# Stepper_L647x.net
KiCad netlist of a schematic drawn in EAGLE
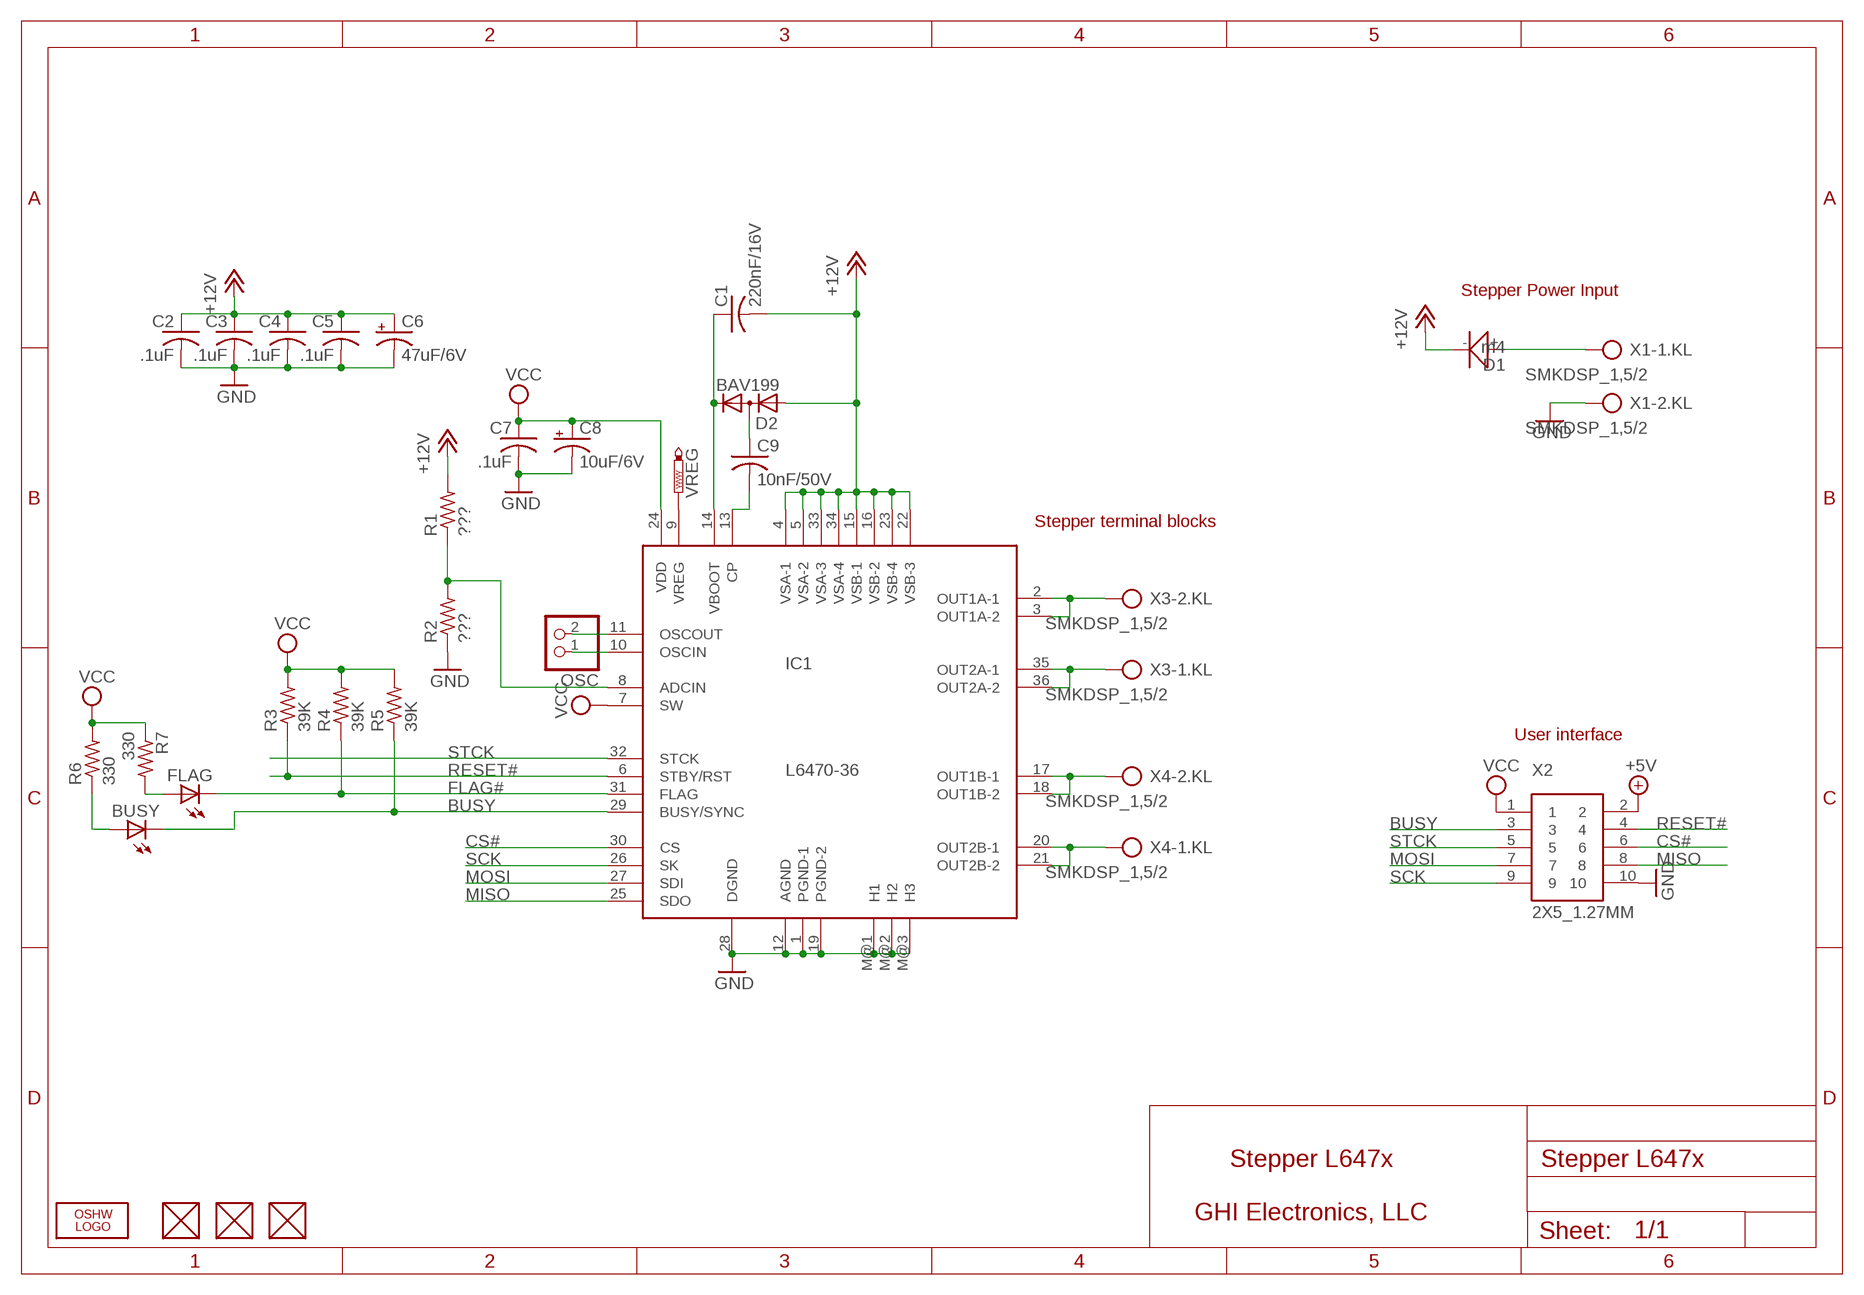
[diagram p0: schematic, sheet 1]

(export (version "E")
  (design (tool "Eeschema 10.0.6"))
  (components
    (comp (ref "BUSY")
      (value "LEDCHIPLED_0805")
      (footprint "eagle-import:CHIPLED_0805")
      (libsource (lib "eagle-import") (part "LEDCHIPLED_0805"))
    )
    (comp (ref "C1")
      (value "220nF/16V")
      (footprint "eagle-import:C0603K")
      (libsource (lib "eagle-import") (part "C-USC0603K"))
    )
    (comp (ref "C2")
      (value ".1uF")
      (footprint "eagle-import:C0603K")
      (libsource (lib "eagle-import") (part "C-USC0603K"))
    )
    (comp (ref "C3")
      (value ".1uF")
      (footprint "eagle-import:C0603K")
      (libsource (lib "eagle-import") (part "C-USC0603K"))
    )
    (comp (ref "C4")
      (value ".1uF")
      (footprint "eagle-import:C0603K")
      (libsource (lib "eagle-import") (part "C-USC0603K"))
    )
    (comp (ref "C5")
      (value ".1uF")
      (footprint "eagle-import:C0603K")
      (libsource (lib "eagle-import") (part "C-USC0603K"))
    )
    (comp (ref "C6")
      (value "47uF/6V")
      (footprint "eagle-import:CT3528")
      (libsource (lib "eagle-import") (part "CPOL-USCT3528"))
    )
    (comp (ref "C7")
      (value ".1uF")
      (footprint "eagle-import:C0603K")
      (libsource (lib "eagle-import") (part "C-USC0603K"))
    )
    (comp (ref "C8")
      (value "10uF/6V")
      (footprint "eagle-import:CT3528")
      (libsource (lib "eagle-import") (part "CPOL-USCT3528"))
    )
    (comp (ref "C9")
      (value "10nF/50V")
      (footprint "eagle-import:C0603K")
      (libsource (lib "eagle-import") (part "C-USC0603K"))
    )
    (comp (ref "D1")
      (value "m4")
      (footprint "eagle-import:D2010")
      (libsource (lib "eagle-import") (part "010-D2010"))
    )
    (comp (ref "D2")
      (value "BAV199")
      (footprint "eagle-import:SOT23")
      (libsource (lib "eagle-import") (part "BAV199"))
    )
    (comp (ref "FLAG")
      (value "LEDCHIPLED_0805")
      (footprint "eagle-import:CHIPLED_0805")
      (libsource (lib "eagle-import") (part "LEDCHIPLED_0805"))
    )
    (comp (ref "FUD1")
      (value "FIDUCIAL")
      (footprint "eagle-import:FIDUCIAL_40MIL")
      (libsource (lib "eagle-import") (part "FIDUCIAL"))
    )
    (comp (ref "FUD2")
      (value "FIDUCIAL")
      (footprint "eagle-import:FIDUCIAL_40MIL")
      (libsource (lib "eagle-import") (part "FIDUCIAL"))
    )
    (comp (ref "FUD3")
      (value "FIDUCIAL")
      (footprint "eagle-import:FIDUCIAL_40MIL")
      (libsource (lib "eagle-import") (part "FIDUCIAL"))
    )
    (comp (ref "IC1")
      (value "L6470-36")
      (footprint "eagle-import:PSO36")
      (libsource (lib "eagle-import") (part "L6470-36"))
    )
    (comp (ref "LOGO1")
      (value "LOGO-OSHW-FILLX0200-NT")
      (footprint "eagle-import:OSHW_FILLX200_NOTEXT")
      (libsource (lib "eagle-import") (part "LOGO-OSHW-FILLX0200-NT"))
    )
    (comp (ref "OSC")
      (value "PINHD-1X2")
      (footprint "eagle-import:1X02")
      (libsource (lib "eagle-import") (part "PINHD-1X2"))
    )
    (comp (ref "R1")
      (value "???")
      (footprint "eagle-import:R0603")
      (libsource (lib "eagle-import") (part "R-US_R0603"))
    )
    (comp (ref "R2")
      (value "???")
      (footprint "eagle-import:R0603")
      (libsource (lib "eagle-import") (part "R-US_R0603"))
    )
    (comp (ref "R3")
      (value "39K")
      (footprint "eagle-import:R0603")
      (libsource (lib "eagle-import") (part "R-US_R0603"))
    )
    (comp (ref "R4")
      (value "39K")
      (footprint "eagle-import:R0603")
      (libsource (lib "eagle-import") (part "R-US_R0603"))
    )
    (comp (ref "R5")
      (value "39K")
      (footprint "eagle-import:R0603")
      (libsource (lib "eagle-import") (part "R-US_R0603"))
    )
    (comp (ref "R6")
      (value "330")
      (footprint "eagle-import:R0603")
      (libsource (lib "eagle-import") (part "R-US_R0603"))
    )
    (comp (ref "R7")
      (value "330")
      (footprint "eagle-import:R0603")
      (libsource (lib "eagle-import") (part "R-US_R0603"))
    )
    (comp (ref "VREG")
      (value "PTR1PAD1-13")
      (footprint "eagle-import:P1-13")
      (libsource (lib "eagle-import") (part "PTR1PAD1-13"))
    )
    (comp (ref "X1")
      (value "SMKDSP_1,5/2")
      (footprint "eagle-import:SMKDSP_1,5_2")
      (libsource (lib "eagle-import") (part "SMKDSP_1,5/2"))
    )
    (comp (ref "X2")
      (value "2X5_1.27MM")
      (footprint "eagle-import:2X5_1.27MM")
      (libsource (lib "eagle-import") (part "2X5_1.27MM"))
    )
    (comp (ref "X3")
      (value "SMKDSP_1,5/2")
      (footprint "eagle-import:SMKDSP_1,5_2")
      (libsource (lib "eagle-import") (part "SMKDSP_1,5/2"))
    )
    (comp (ref "X4")
      (value "SMKDSP_1,5/2")
      (footprint "eagle-import:SMKDSP_1,5_2")
      (libsource (lib "eagle-import") (part "SMKDSP_1,5/2"))
    )
  )
  (nets
    (net (code "1") (name "+5V") (class "Default")
      (node (ref "X2") (pin "2") (pinfunction "2_2") (pintype "bidirectional"))
    )
    (net (code "2") (name "+12V") (class "Default")
      (node (ref "C1") (pin "2") (pinfunction "2_2") (pintype "passive"))
      (node (ref "C2") (pin "1") (pinfunction "1_1") (pintype "passive"))
      (node (ref "C3") (pin "1") (pinfunction "1_1") (pintype "passive"))
      (node (ref "C4") (pin "1") (pinfunction "1_1") (pintype "passive"))
      (node (ref "C5") (pin "1") (pinfunction "1_1") (pintype "passive"))
      (node (ref "C6") (pin "+") (pinfunction "+_+") (pintype "passive"))
      (node (ref "D1") (pin "-") (pinfunction "-_-") (pintype "passive"))
      (node (ref "D2") (pin "1") (pinfunction "A_1") (pintype "passive"))
      (node (ref "IC1") (pin "15") (pinfunction "VSB-1_15") (pintype "bidirectional"))
      (node (ref "IC1") (pin "16") (pinfunction "VSB-2_16") (pintype "bidirectional"))
      (node (ref "IC1") (pin "22") (pinfunction "VSB-3_22") (pintype "bidirectional"))
      (node (ref "IC1") (pin "23") (pinfunction "VSB-4_23") (pintype "bidirectional"))
      (node (ref "IC1") (pin "33") (pinfunction "VSA-3_33") (pintype "bidirectional"))
      (node (ref "IC1") (pin "34") (pinfunction "VSA-4_34") (pintype "bidirectional"))
      (node (ref "IC1") (pin "4") (pinfunction "VSA-1_4") (pintype "bidirectional"))
      (node (ref "IC1") (pin "5") (pinfunction "VSA-2_5") (pintype "bidirectional"))
      (node (ref "R1") (pin "2") (pinfunction "2_2") (pintype "passive"))
    )
    (net (code "3") (name "/BUSY") (class "Default")
      (node (ref "BUSY") (pin "C") (pinfunction "C_C") (pintype "passive"))
      (node (ref "IC1") (pin "29") (pinfunction "BUSY/SYNC_29") (pintype "bidirectional"))
      (node (ref "R5") (pin "1") (pinfunction "1_1") (pintype "passive"))
      (node (ref "X2") (pin "3") (pinfunction "3_3") (pintype "bidirectional"))
    )
    (net (code "4") (name "/CS#") (class "Default")
      (node (ref "IC1") (pin "30") (pinfunction "CS_30") (pintype "bidirectional"))
      (node (ref "X2") (pin "6") (pinfunction "6_6") (pintype "bidirectional"))
    )
    (net (code "5") (name "/FLAG#") (class "Default")
      (node (ref "FLAG") (pin "C") (pinfunction "C_C") (pintype "passive"))
      (node (ref "IC1") (pin "31") (pinfunction "FLAG_31") (pintype "bidirectional"))
      (node (ref "R4") (pin "1") (pinfunction "1_1") (pintype "passive"))
    )
    (net (code "6") (name "/MISO") (class "Default")
      (node (ref "IC1") (pin "25") (pinfunction "SDO_25") (pintype "bidirectional"))
      (node (ref "X2") (pin "8") (pinfunction "8_8") (pintype "bidirectional"))
    )
    (net (code "7") (name "/MOSI") (class "Default")
      (node (ref "IC1") (pin "27") (pinfunction "SDI_27") (pintype "bidirectional"))
      (node (ref "X2") (pin "7") (pinfunction "7_7") (pintype "bidirectional"))
    )
    (net (code "8") (name "/RESET#") (class "Default")
      (node (ref "IC1") (pin "6") (pinfunction "STBY/RST_6") (pintype "bidirectional"))
      (node (ref "R3") (pin "1") (pinfunction "1_1") (pintype "passive"))
      (node (ref "X2") (pin "4") (pinfunction "4_4") (pintype "bidirectional"))
    )
    (net (code "9") (name "/SCK") (class "Default")
      (node (ref "IC1") (pin "26") (pinfunction "SK_26") (pintype "bidirectional"))
      (node (ref "X2") (pin "9") (pinfunction "9_9") (pintype "bidirectional"))
    )
    (net (code "10") (name "/STCK") (class "Default")
      (node (ref "IC1") (pin "32") (pinfunction "STCK_32") (pintype "bidirectional"))
      (node (ref "X2") (pin "5") (pinfunction "5_5") (pintype "bidirectional"))
    )
    (net (code "11") (name "GND") (class "Default")
      (node (ref "C2") (pin "2") (pinfunction "2_2") (pintype "passive"))
      (node (ref "C3") (pin "2") (pinfunction "2_2") (pintype "passive"))
      (node (ref "C4") (pin "2") (pinfunction "2_2") (pintype "passive"))
      (node (ref "C5") (pin "2") (pinfunction "2_2") (pintype "passive"))
      (node (ref "C6") (pin "-") (pinfunction "-_-") (pintype "passive"))
      (node (ref "C7") (pin "2") (pinfunction "2_2") (pintype "passive"))
      (node (ref "C8") (pin "-") (pinfunction "-_-") (pintype "passive"))
      (node (ref "IC1") (pin "1") (pinfunction "PGND-1_1") (pintype "bidirectional"))
      (node (ref "IC1") (pin "12") (pinfunction "AGND_12") (pintype "bidirectional"))
      (node (ref "IC1") (pin "19") (pinfunction "PGND-2_19") (pintype "bidirectional"))
      (node (ref "IC1") (pin "28") (pinfunction "DGND_28") (pintype "bidirectional"))
      (node (ref "IC1") (pin "M@1") (pinfunction "H1_M@1") (pintype "bidirectional"))
      (node (ref "IC1") (pin "M@2") (pinfunction "H2_M@2") (pintype "bidirectional"))
      (node (ref "IC1") (pin "M@3") (pinfunction "H3_M@3") (pintype "bidirectional"))
      (node (ref "R2") (pin "1") (pinfunction "1_1") (pintype "passive"))
      (node (ref "X1") (pin "2") (pinfunction "KL_2") (pintype "passive"))
      (node (ref "X2") (pin "10") (pinfunction "10_10") (pintype "bidirectional"))
    )
    (net (code "12") (name "Net-(BUSY-PadA)") (class "Default")
      (node (ref "BUSY") (pin "A") (pinfunction "A_A") (pintype "passive"))
      (node (ref "R6") (pin "1") (pinfunction "1_1") (pintype "passive"))
    )
    (net (code "13") (name "Net-(D2-AC)") (class "Default")
      (node (ref "C9") (pin "1") (pinfunction "1_1") (pintype "passive"))
      (node (ref "D2") (pin "3") (pinfunction "AC_3") (pintype "passive"))
    )
    (net (code "14") (name "Net-(D2-C)") (class "Default")
      (node (ref "C1") (pin "1") (pinfunction "1_1") (pintype "passive"))
      (node (ref "D2") (pin "2") (pinfunction "C_2") (pintype "passive"))
      (node (ref "IC1") (pin "14") (pinfunction "VBOOT_14") (pintype "bidirectional"))
    )
    (net (code "15") (name "Net-(FLAG-PadA)") (class "Default")
      (node (ref "FLAG") (pin "A") (pinfunction "A_A") (pintype "passive"))
      (node (ref "R7") (pin "2") (pinfunction "2_2") (pintype "passive"))
    )
    (net (code "16") (name "Net-(IC1-ADCIN)") (class "Default")
      (node (ref "IC1") (pin "8") (pinfunction "ADCIN_8") (pintype "bidirectional"))
      (node (ref "R1") (pin "1") (pinfunction "1_1") (pintype "passive"))
      (node (ref "R2") (pin "2") (pinfunction "2_2") (pintype "passive"))
    )
    (net (code "17") (name "Net-(IC1-CP)") (class "Default")
      (node (ref "C9") (pin "2") (pinfunction "2_2") (pintype "passive"))
      (node (ref "IC1") (pin "13") (pinfunction "CP_13") (pintype "bidirectional"))
    )
    (net (code "18") (name "Net-(IC1-OSCIN)") (class "Default")
      (node (ref "IC1") (pin "10") (pinfunction "OSCIN_10") (pintype "bidirectional"))
      (node (ref "OSC") (pin "1") (pinfunction "1_1") (pintype "passive"))
    )
    (net (code "19") (name "Net-(IC1-OSCOUT)") (class "Default")
      (node (ref "IC1") (pin "11") (pinfunction "OSCOUT_11") (pintype "bidirectional"))
      (node (ref "OSC") (pin "2") (pinfunction "2_2") (pintype "passive"))
    )
    (net (code "20") (name "Net-(IC1-OUT1A-1)") (class "Default")
      (node (ref "IC1") (pin "2") (pinfunction "OUT1A-1_2") (pintype "bidirectional"))
      (node (ref "IC1") (pin "3") (pinfunction "OUT1A-2_3") (pintype "bidirectional"))
      (node (ref "X3") (pin "2") (pinfunction "KL_2") (pintype "passive"))
    )
    (net (code "21") (name "Net-(IC1-OUT1B-1)") (class "Default")
      (node (ref "IC1") (pin "17") (pinfunction "OUT1B-1_17") (pintype "bidirectional"))
      (node (ref "IC1") (pin "18") (pinfunction "OUT1B-2_18") (pintype "bidirectional"))
      (node (ref "X4") (pin "2") (pinfunction "KL_2") (pintype "passive"))
    )
    (net (code "22") (name "Net-(IC1-OUT2A-1)") (class "Default")
      (node (ref "IC1") (pin "35") (pinfunction "OUT2A-1_35") (pintype "bidirectional"))
      (node (ref "IC1") (pin "36") (pinfunction "OUT2A-2_36") (pintype "bidirectional"))
      (node (ref "X3") (pin "1") (pinfunction "KL_1") (pintype "passive"))
    )
    (net (code "23") (name "Net-(IC1-OUT2B-1)") (class "Default")
      (node (ref "IC1") (pin "20") (pinfunction "OUT2B-1_20") (pintype "bidirectional"))
      (node (ref "IC1") (pin "21") (pinfunction "OUT2B-2_21") (pintype "bidirectional"))
      (node (ref "X4") (pin "1") (pinfunction "KL_1") (pintype "passive"))
    )
    (net (code "24") (name "Net-(IC1-VREG)") (class "Default")
      (node (ref "IC1") (pin "9") (pinfunction "VREG_9") (pintype "bidirectional"))
      (node (ref "VREG") (pin "TP") (pinfunction "TP_TP") (pintype "input"))
    )
    (net (code "25") (name "Net-(X1A-KL)") (class "Default")
      (node (ref "D1") (pin "+") (pinfunction "+_+") (pintype "passive"))
      (node (ref "X1") (pin "1") (pinfunction "KL_1") (pintype "passive"))
    )
    (net (code "26") (name "VCC") (class "Default")
      (node (ref "C7") (pin "1") (pinfunction "1_1") (pintype "passive"))
      (node (ref "C8") (pin "+") (pinfunction "+_+") (pintype "passive"))
      (node (ref "IC1") (pin "24") (pinfunction "VDD_24") (pintype "bidirectional"))
      (node (ref "IC1") (pin "7") (pinfunction "SW_7") (pintype "bidirectional"))
      (node (ref "R3") (pin "2") (pinfunction "2_2") (pintype "passive"))
      (node (ref "R4") (pin "2") (pinfunction "2_2") (pintype "passive"))
      (node (ref "R5") (pin "2") (pinfunction "2_2") (pintype "passive"))
      (node (ref "R6") (pin "2") (pinfunction "2_2") (pintype "passive"))
      (node (ref "R7") (pin "1") (pinfunction "1_1") (pintype "passive"))
      (node (ref "X2") (pin "1") (pinfunction "1_1") (pintype "bidirectional"))
    )
    (net (code "27") (name "unconnected-(FUD1-PadP$1)") (class "Default")
      (node (ref "FUD1") (pin "P$1") (pinfunction "P$1_P$1") (pintype "no_connect"))
    )
    (net (code "28") (name "unconnected-(FUD2-PadP$1)") (class "Default")
      (node (ref "FUD2") (pin "P$1") (pinfunction "P$1_P$1") (pintype "no_connect"))
    )
    (net (code "29") (name "unconnected-(FUD3-PadP$1)") (class "Default")
      (node (ref "FUD3") (pin "P$1") (pinfunction "P$1_P$1") (pintype "no_connect"))
    )
  )
)
